# Shield_Empty.net
KiCad netlist of a schematic drawn in EAGLE
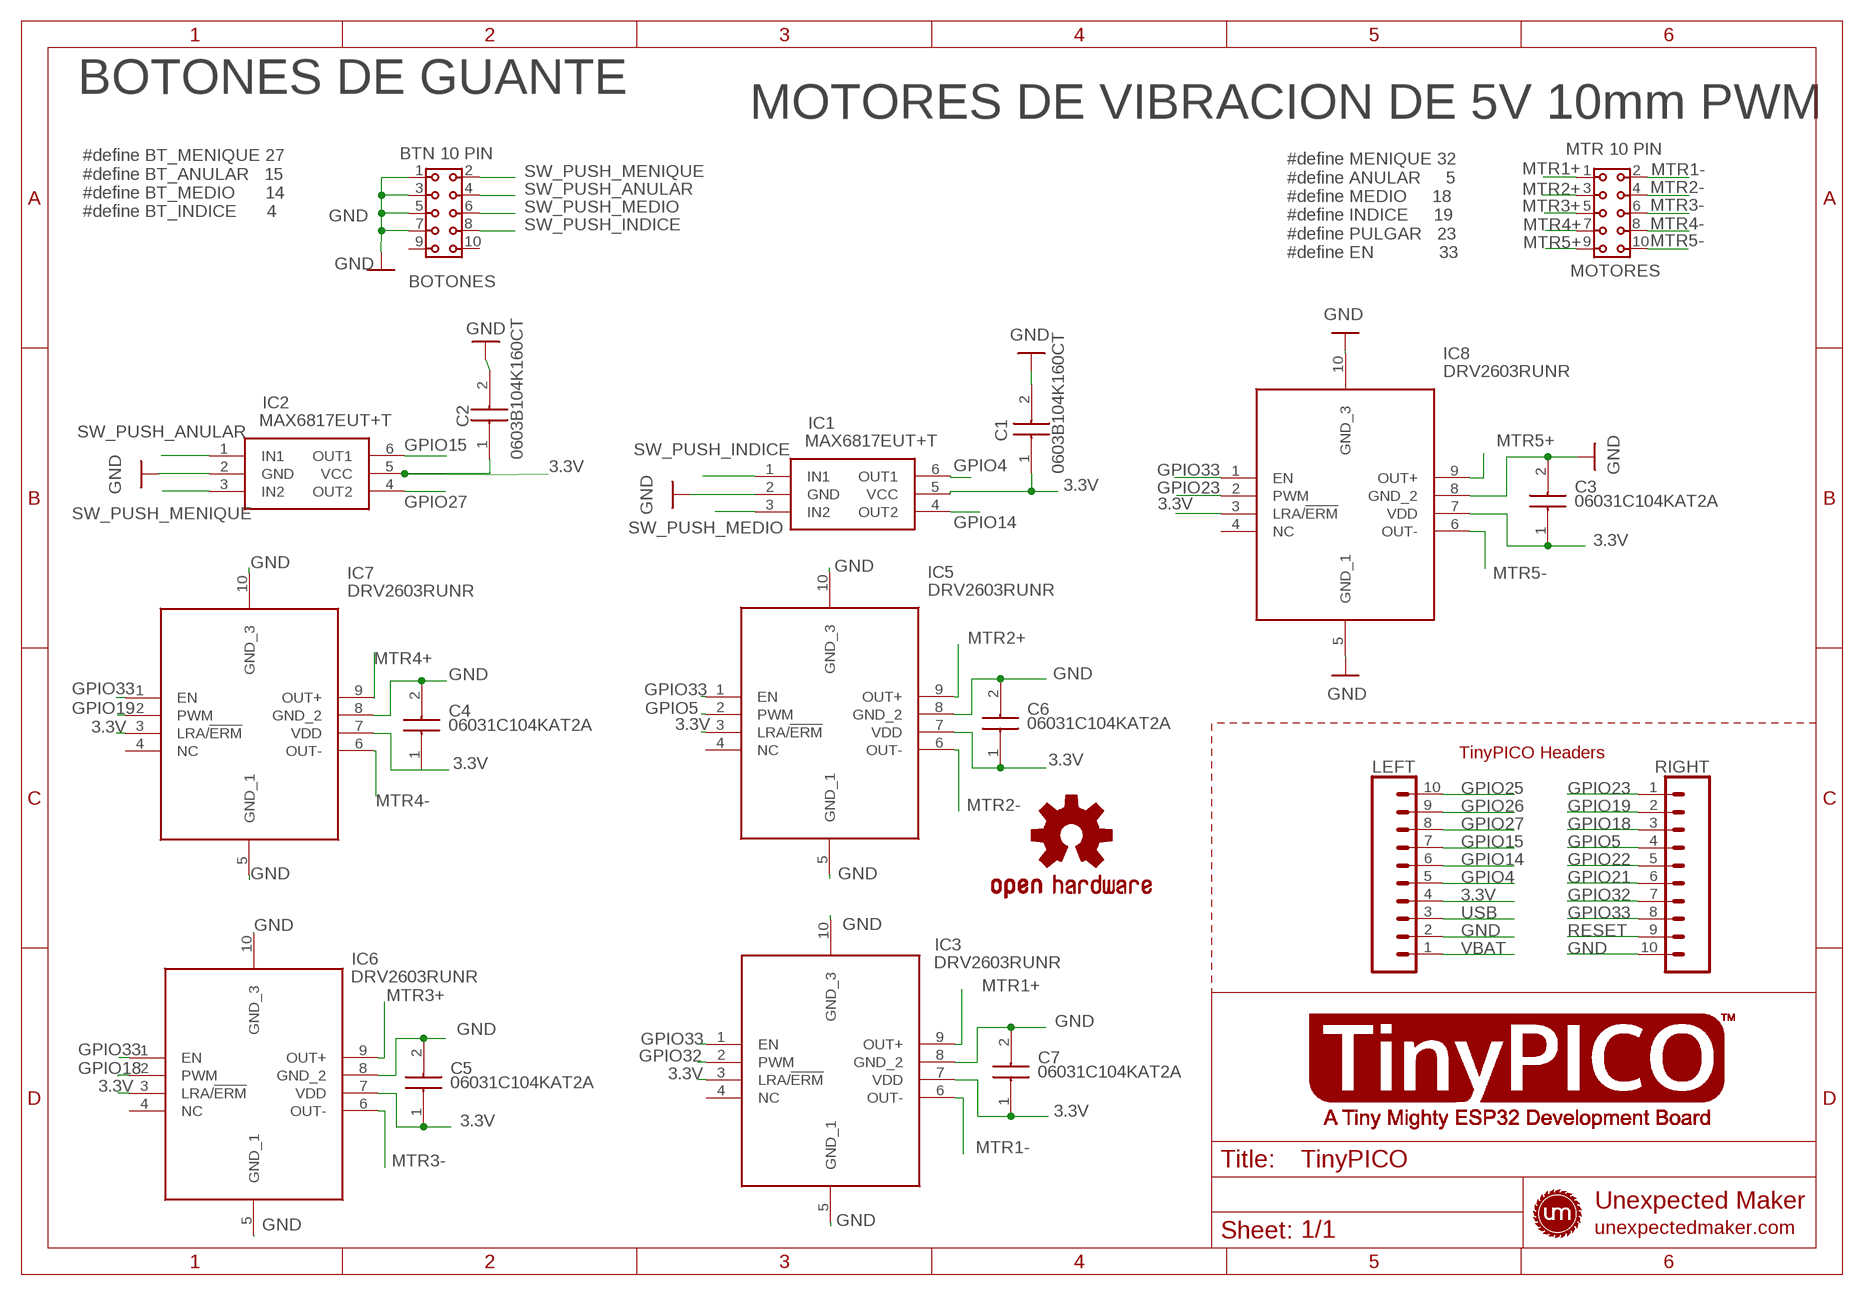
[diagram p0: schematic, sheet 1]

(export (version "E")
  (design (tool "Eeschema 10.0.6"))
  (components
    (comp (ref "BOTONES")
      (value "BTN 10 PIN")
      (footprint "eagle-import:61301021821")
      (libsource (lib "eagle-import") (part "6130XX21821_61301021821"))
    )
    (comp (ref "C1")
      (value "0603B104K160CT")
      (footprint "eagle-import:CAPC1608X87N")
      (fields (field (name "MOUSER_PART_NUMBER") "791-0603B104K160CT"))
      (libsource (lib "eagle-import") (part "0603B104K160CT"))
    )
    (comp (ref "C2")
      (value "0603B104K160CT")
      (footprint "eagle-import:CAPC1608X87N")
      (fields (field (name "MOUSER_PART_NUMBER") "791-0603B104K160CT"))
      (libsource (lib "eagle-import") (part "0603B104K160CT"))
    )
    (comp (ref "C3")
      (value "06031C104KAT2A")
      (footprint "eagle-import:CAPC1608X90N")
      (fields (field (name "MOUSER_PART_NUMBER") "581-06031C104KAT2A"))
      (libsource (lib "eagle-import") (part "06031C104KAT2A"))
    )
    (comp (ref "C4")
      (value "06031C104KAT2A")
      (footprint "eagle-import:CAPC1608X90N")
      (fields (field (name "MOUSER_PART_NUMBER") "581-06031C104KAT2A"))
      (libsource (lib "eagle-import") (part "06031C104KAT2A"))
    )
    (comp (ref "C5")
      (value "06031C104KAT2A")
      (footprint "eagle-import:CAPC1608X90N")
      (fields (field (name "MOUSER_PART_NUMBER") "581-06031C104KAT2A"))
      (libsource (lib "eagle-import") (part "06031C104KAT2A"))
    )
    (comp (ref "C6")
      (value "06031C104KAT2A")
      (footprint "eagle-import:CAPC1608X90N")
      (fields (field (name "MOUSER_PART_NUMBER") "581-06031C104KAT2A"))
      (libsource (lib "eagle-import") (part "06031C104KAT2A"))
    )
    (comp (ref "C7")
      (value "06031C104KAT2A")
      (footprint "eagle-import:CAPC1608X90N")
      (fields (field (name "MOUSER_PART_NUMBER") "581-06031C104KAT2A"))
      (libsource (lib "eagle-import") (part "06031C104KAT2A"))
    )
    (comp (ref "IC1")
      (value "MAX6817EUT+T")
      (footprint "eagle-import:SOT95P280X145-6N")
      (fields (field (name "MOUSER_PART_NUMBER") "700-MAX6817EUTT"))
      (libsource (lib "eagle-import") (part "MAX6817EUT+T"))
    )
    (comp (ref "IC2")
      (value "MAX6817EUT+T")
      (footprint "eagle-import:SOT95P280X145-6N")
      (fields (field (name "MOUSER_PART_NUMBER") "700-MAX6817EUTT"))
      (libsource (lib "eagle-import") (part "MAX6817EUT+T"))
    )
    (comp (ref "IC3")
      (value "DRV2603RUNR")
      (footprint "eagle-import:QFN50P200X200X80-10N")
      (fields (field (name "MOUSER_PART_NUMBER") "595-DRV2603RUNR"))
      (libsource (lib "eagle-import") (part "DRV2603RUNR"))
    )
    (comp (ref "IC5")
      (value "DRV2603RUNR")
      (footprint "eagle-import:QFN50P200X200X80-10N")
      (fields (field (name "MOUSER_PART_NUMBER") "595-DRV2603RUNR"))
      (libsource (lib "eagle-import") (part "DRV2603RUNR"))
    )
    (comp (ref "IC6")
      (value "DRV2603RUNR")
      (footprint "eagle-import:QFN50P200X200X80-10N")
      (fields (field (name "MOUSER_PART_NUMBER") "595-DRV2603RUNR"))
      (libsource (lib "eagle-import") (part "DRV2603RUNR"))
    )
    (comp (ref "IC7")
      (value "DRV2603RUNR")
      (footprint "eagle-import:QFN50P200X200X80-10N")
      (fields (field (name "MOUSER_PART_NUMBER") "595-DRV2603RUNR"))
      (libsource (lib "eagle-import") (part "DRV2603RUNR"))
    )
    (comp (ref "IC8")
      (value "DRV2603RUNR")
      (footprint "eagle-import:QFN50P200X200X80-10N")
      (fields (field (name "MOUSER_PART_NUMBER") "595-DRV2603RUNR"))
      (libsource (lib "eagle-import") (part "DRV2603RUNR"))
    )
    (comp (ref "LEFT")
      (value "TINYPICO_HEADER_10NO_SILK_PTH_FEMALE")
      (footprint "eagle-import:1X10_NO_SILK")
      (libsource (lib "eagle-import") (part "TINYPICO_HEADER_10NO_SILK_PTH_FEMALE"))
    )
    (comp (ref "LOGO1")
      (value "OSHW-LOGOS")
      (footprint "eagle-import:OSHW-LOGO-S")
      (libsource (lib "eagle-import") (part "OSHW-LOGOS"))
    )
    (comp (ref "MOTORES")
      (value "MTR 10 PIN")
      (footprint "eagle-import:61301021821")
      (libsource (lib "eagle-import") (part "6130XX21821_61301021821"))
    )
    (comp (ref "RIGHT")
      (value "TINYPICO_HEADER_10NO_SILK_PTH_FEMALE")
      (footprint "eagle-import:1X10_NO_SILK")
      (libsource (lib "eagle-import") (part "TINYPICO_HEADER_10NO_SILK_PTH_FEMALE"))
    )
  )
  (nets
    (net (code "1") (name "/3.3V") (class "Default")
      (node (ref "C1") (pin "1") (pinfunction "1_1") (pintype "bidirectional"))
      (node (ref "C2") (pin "1") (pinfunction "1_1") (pintype "bidirectional"))
      (node (ref "C3") (pin "1") (pinfunction "1_1") (pintype "bidirectional"))
      (node (ref "C4") (pin "1") (pinfunction "1_1") (pintype "bidirectional"))
      (node (ref "C5") (pin "1") (pinfunction "1_1") (pintype "bidirectional"))
      (node (ref "C6") (pin "1") (pinfunction "1_1") (pintype "bidirectional"))
      (node (ref "C7") (pin "1") (pinfunction "1_1") (pintype "bidirectional"))
      (node (ref "IC1") (pin "5") (pinfunction "VCC_5") (pintype "bidirectional"))
      (node (ref "IC2") (pin "5") (pinfunction "VCC_5") (pintype "bidirectional"))
      (node (ref "IC3") (pin "3") (pinfunction "LRA/~{ERM}_3") (pintype "input"))
      (node (ref "IC3") (pin "7") (pinfunction "VDD_7") (pintype "power_in"))
      (node (ref "IC5") (pin "3") (pinfunction "LRA/~{ERM}_3") (pintype "input"))
      (node (ref "IC5") (pin "7") (pinfunction "VDD_7") (pintype "power_in"))
      (node (ref "IC6") (pin "3") (pinfunction "LRA/~{ERM}_3") (pintype "input"))
      (node (ref "IC6") (pin "7") (pinfunction "VDD_7") (pintype "power_in"))
      (node (ref "IC7") (pin "3") (pinfunction "LRA/~{ERM}_3") (pintype "input"))
      (node (ref "IC7") (pin "7") (pinfunction "VDD_7") (pintype "power_in"))
      (node (ref "IC8") (pin "3") (pinfunction "LRA/~{ERM}_3") (pintype "input"))
      (node (ref "IC8") (pin "7") (pinfunction "VDD_7") (pintype "power_in"))
      (node (ref "LEFT") (pin "4") (pinfunction "4_4") (pintype "passive"))
    )
    (net (code "2") (name "/GPIO4") (class "Default")
      (node (ref "IC1") (pin "6") (pinfunction "OUT1_6") (pintype "bidirectional"))
      (node (ref "LEFT") (pin "5") (pinfunction "5_5") (pintype "passive"))
    )
    (net (code "3") (name "/GPIO5") (class "Default")
      (node (ref "IC5") (pin "2") (pinfunction "PWM_2") (pintype "input"))
      (node (ref "RIGHT") (pin "4") (pinfunction "4_4") (pintype "passive"))
    )
    (net (code "4") (name "/GPIO14") (class "Default")
      (node (ref "IC1") (pin "4") (pinfunction "OUT2_4") (pintype "bidirectional"))
      (node (ref "LEFT") (pin "6") (pinfunction "6_6") (pintype "passive"))
    )
    (net (code "5") (name "/GPIO15") (class "Default")
      (node (ref "IC2") (pin "6") (pinfunction "OUT1_6") (pintype "bidirectional"))
      (node (ref "LEFT") (pin "7") (pinfunction "7_7") (pintype "passive"))
    )
    (net (code "6") (name "/GPIO18") (class "Default")
      (node (ref "IC6") (pin "2") (pinfunction "PWM_2") (pintype "input"))
      (node (ref "RIGHT") (pin "3") (pinfunction "3_3") (pintype "passive"))
    )
    (net (code "7") (name "/GPIO19") (class "Default")
      (node (ref "IC7") (pin "2") (pinfunction "PWM_2") (pintype "input"))
      (node (ref "RIGHT") (pin "2") (pinfunction "2_2") (pintype "passive"))
    )
    (net (code "8") (name "/GPIO21") (class "Default")
      (node (ref "RIGHT") (pin "6") (pinfunction "6_6") (pintype "passive"))
    )
    (net (code "9") (name "/GPIO22") (class "Default")
      (node (ref "RIGHT") (pin "5") (pinfunction "5_5") (pintype "passive"))
    )
    (net (code "10") (name "/GPIO23") (class "Default")
      (node (ref "IC8") (pin "2") (pinfunction "PWM_2") (pintype "input"))
      (node (ref "RIGHT") (pin "1") (pinfunction "1_1") (pintype "passive"))
    )
    (net (code "11") (name "/GPIO25") (class "Default")
      (node (ref "LEFT") (pin "10") (pinfunction "10_10") (pintype "passive"))
    )
    (net (code "12") (name "/GPIO26") (class "Default")
      (node (ref "LEFT") (pin "9") (pinfunction "9_9") (pintype "passive"))
    )
    (net (code "13") (name "/GPIO27") (class "Default")
      (node (ref "IC2") (pin "4") (pinfunction "OUT2_4") (pintype "bidirectional"))
      (node (ref "LEFT") (pin "8") (pinfunction "8_8") (pintype "passive"))
    )
    (net (code "14") (name "/GPIO32") (class "Default")
      (node (ref "IC3") (pin "2") (pinfunction "PWM_2") (pintype "input"))
      (node (ref "RIGHT") (pin "7") (pinfunction "7_7") (pintype "passive"))
    )
    (net (code "15") (name "/GPIO33") (class "Default")
      (node (ref "IC3") (pin "1") (pinfunction "EN_1") (pintype "input"))
      (node (ref "IC5") (pin "1") (pinfunction "EN_1") (pintype "input"))
      (node (ref "IC6") (pin "1") (pinfunction "EN_1") (pintype "input"))
      (node (ref "IC7") (pin "1") (pinfunction "EN_1") (pintype "input"))
      (node (ref "IC8") (pin "1") (pinfunction "EN_1") (pintype "input"))
      (node (ref "RIGHT") (pin "8") (pinfunction "8_8") (pintype "passive"))
    )
    (net (code "16") (name "/MTR1+") (class "Default")
      (node (ref "IC3") (pin "9") (pinfunction "OUT+_9") (pintype "output"))
      (node (ref "MOTORES") (pin "1") (pinfunction "1_1") (pintype "passive"))
    )
    (net (code "17") (name "/MTR1-") (class "Default")
      (node (ref "IC3") (pin "6") (pinfunction "OUT-_6") (pintype "output"))
      (node (ref "MOTORES") (pin "2") (pinfunction "2_2") (pintype "passive"))
    )
    (net (code "18") (name "/MTR2+") (class "Default")
      (node (ref "IC5") (pin "9") (pinfunction "OUT+_9") (pintype "output"))
      (node (ref "MOTORES") (pin "3") (pinfunction "3_3") (pintype "passive"))
    )
    (net (code "19") (name "/MTR2-") (class "Default")
      (node (ref "IC5") (pin "6") (pinfunction "OUT-_6") (pintype "output"))
      (node (ref "MOTORES") (pin "4") (pinfunction "4_4") (pintype "passive"))
    )
    (net (code "20") (name "/MTR3+") (class "Default")
      (node (ref "IC6") (pin "9") (pinfunction "OUT+_9") (pintype "output"))
      (node (ref "MOTORES") (pin "5") (pinfunction "5_5") (pintype "passive"))
    )
    (net (code "21") (name "/MTR3-") (class "Default")
      (node (ref "IC6") (pin "6") (pinfunction "OUT-_6") (pintype "output"))
      (node (ref "MOTORES") (pin "6") (pinfunction "6_6") (pintype "passive"))
    )
    (net (code "22") (name "/MTR4+") (class "Default")
      (node (ref "IC7") (pin "9") (pinfunction "OUT+_9") (pintype "output"))
      (node (ref "MOTORES") (pin "7") (pinfunction "7_7") (pintype "passive"))
    )
    (net (code "23") (name "/MTR4-") (class "Default")
      (node (ref "IC7") (pin "6") (pinfunction "OUT-_6") (pintype "output"))
      (node (ref "MOTORES") (pin "8") (pinfunction "8_8") (pintype "passive"))
    )
    (net (code "24") (name "/MTR5+") (class "Default")
      (node (ref "IC8") (pin "9") (pinfunction "OUT+_9") (pintype "output"))
      (node (ref "MOTORES") (pin "9") (pinfunction "9_9") (pintype "passive"))
    )
    (net (code "25") (name "/MTR5-") (class "Default")
      (node (ref "IC8") (pin "6") (pinfunction "OUT-_6") (pintype "output"))
      (node (ref "MOTORES") (pin "10") (pinfunction "10_10") (pintype "passive"))
    )
    (net (code "26") (name "/RESET") (class "Default")
      (node (ref "RIGHT") (pin "9") (pinfunction "9_9") (pintype "passive"))
    )
    (net (code "27") (name "/SW_PUSH_ANULAR") (class "Default")
      (node (ref "BOTONES") (pin "4") (pinfunction "4_4") (pintype "passive"))
      (node (ref "IC2") (pin "1") (pinfunction "IN1_1") (pintype "bidirectional"))
    )
    (net (code "28") (name "/SW_PUSH_INDICE") (class "Default")
      (node (ref "BOTONES") (pin "8") (pinfunction "8_8") (pintype "passive"))
      (node (ref "IC1") (pin "1") (pinfunction "IN1_1") (pintype "bidirectional"))
    )
    (net (code "29") (name "/SW_PUSH_MEDIO") (class "Default")
      (node (ref "BOTONES") (pin "6") (pinfunction "6_6") (pintype "passive"))
      (node (ref "IC1") (pin "3") (pinfunction "IN2_3") (pintype "bidirectional"))
    )
    (net (code "30") (name "/SW_PUSH_MENIQUE") (class "Default")
      (node (ref "BOTONES") (pin "2") (pinfunction "2_2") (pintype "passive"))
      (node (ref "IC2") (pin "3") (pinfunction "IN2_3") (pintype "bidirectional"))
    )
    (net (code "31") (name "/USB") (class "Default")
      (node (ref "LEFT") (pin "3") (pinfunction "3_3") (pintype "passive"))
    )
    (net (code "32") (name "/VBAT") (class "Default")
      (node (ref "LEFT") (pin "1") (pinfunction "1_1") (pintype "passive"))
    )
    (net (code "33") (name "GND") (class "Default")
      (node (ref "BOTONES") (pin "1") (pinfunction "1_1") (pintype "passive"))
      (node (ref "BOTONES") (pin "3") (pinfunction "3_3") (pintype "passive"))
      (node (ref "BOTONES") (pin "5") (pinfunction "5_5") (pintype "passive"))
      (node (ref "BOTONES") (pin "7") (pinfunction "7_7") (pintype "passive"))
      (node (ref "C1") (pin "2") (pinfunction "2_2") (pintype "bidirectional"))
      (node (ref "C2") (pin "2") (pinfunction "2_2") (pintype "bidirectional"))
      (node (ref "C3") (pin "2") (pinfunction "2_2") (pintype "bidirectional"))
      (node (ref "C4") (pin "2") (pinfunction "2_2") (pintype "bidirectional"))
      (node (ref "C5") (pin "2") (pinfunction "2_2") (pintype "bidirectional"))
      (node (ref "C6") (pin "2") (pinfunction "2_2") (pintype "bidirectional"))
      (node (ref "C7") (pin "2") (pinfunction "2_2") (pintype "bidirectional"))
      (node (ref "IC1") (pin "2") (pinfunction "GND_2") (pintype "bidirectional"))
      (node (ref "IC2") (pin "2") (pinfunction "GND_2") (pintype "bidirectional"))
      (node (ref "IC3") (pin "10") (pinfunction "GND_3_10") (pintype "power_in"))
      (node (ref "IC3") (pin "5") (pinfunction "GND_1_5") (pintype "power_in"))
      (node (ref "IC3") (pin "8") (pinfunction "GND_2_8") (pintype "power_in"))
      (node (ref "IC5") (pin "10") (pinfunction "GND_3_10") (pintype "power_in"))
      (node (ref "IC5") (pin "5") (pinfunction "GND_1_5") (pintype "power_in"))
      (node (ref "IC5") (pin "8") (pinfunction "GND_2_8") (pintype "power_in"))
      (node (ref "IC6") (pin "10") (pinfunction "GND_3_10") (pintype "power_in"))
      (node (ref "IC6") (pin "5") (pinfunction "GND_1_5") (pintype "power_in"))
      (node (ref "IC6") (pin "8") (pinfunction "GND_2_8") (pintype "power_in"))
      (node (ref "IC7") (pin "10") (pinfunction "GND_3_10") (pintype "power_in"))
      (node (ref "IC7") (pin "5") (pinfunction "GND_1_5") (pintype "power_in"))
      (node (ref "IC7") (pin "8") (pinfunction "GND_2_8") (pintype "power_in"))
      (node (ref "IC8") (pin "10") (pinfunction "GND_3_10") (pintype "power_in"))
      (node (ref "IC8") (pin "5") (pinfunction "GND_1_5") (pintype "power_in"))
      (node (ref "IC8") (pin "8") (pinfunction "GND_2_8") (pintype "power_in"))
      (node (ref "LEFT") (pin "2") (pinfunction "2_2") (pintype "passive"))
      (node (ref "RIGHT") (pin "10") (pinfunction "10_10") (pintype "passive"))
    )
    (net (code "34") (name "unconnected-(BOTONES-Pad9)") (class "Default")
      (node (ref "BOTONES") (pin "9") (pinfunction "9_9") (pintype "passive"))
    )
    (net (code "35") (name "unconnected-(BOTONES-Pad10)") (class "Default")
      (node (ref "BOTONES") (pin "10") (pinfunction "10_10") (pintype "passive"))
    )
    (net (code "36") (name "unconnected-(IC3-NC-Pad4)") (class "Default")
      (node (ref "IC3") (pin "4") (pinfunction "NC_4") (pintype "no_connect"))
    )
    (net (code "37") (name "unconnected-(IC5-NC-Pad4)") (class "Default")
      (node (ref "IC5") (pin "4") (pinfunction "NC_4") (pintype "no_connect"))
    )
    (net (code "38") (name "unconnected-(IC6-NC-Pad4)") (class "Default")
      (node (ref "IC6") (pin "4") (pinfunction "NC_4") (pintype "no_connect"))
    )
    (net (code "39") (name "unconnected-(IC7-NC-Pad4)") (class "Default")
      (node (ref "IC7") (pin "4") (pinfunction "NC_4") (pintype "no_connect"))
    )
    (net (code "40") (name "unconnected-(IC8-NC-Pad4)") (class "Default")
      (node (ref "IC8") (pin "4") (pinfunction "NC_4") (pintype "no_connect"))
    )
  )
)
